# Sheet2.net
KiCad netlist of a schematic drawn in Altium Designer
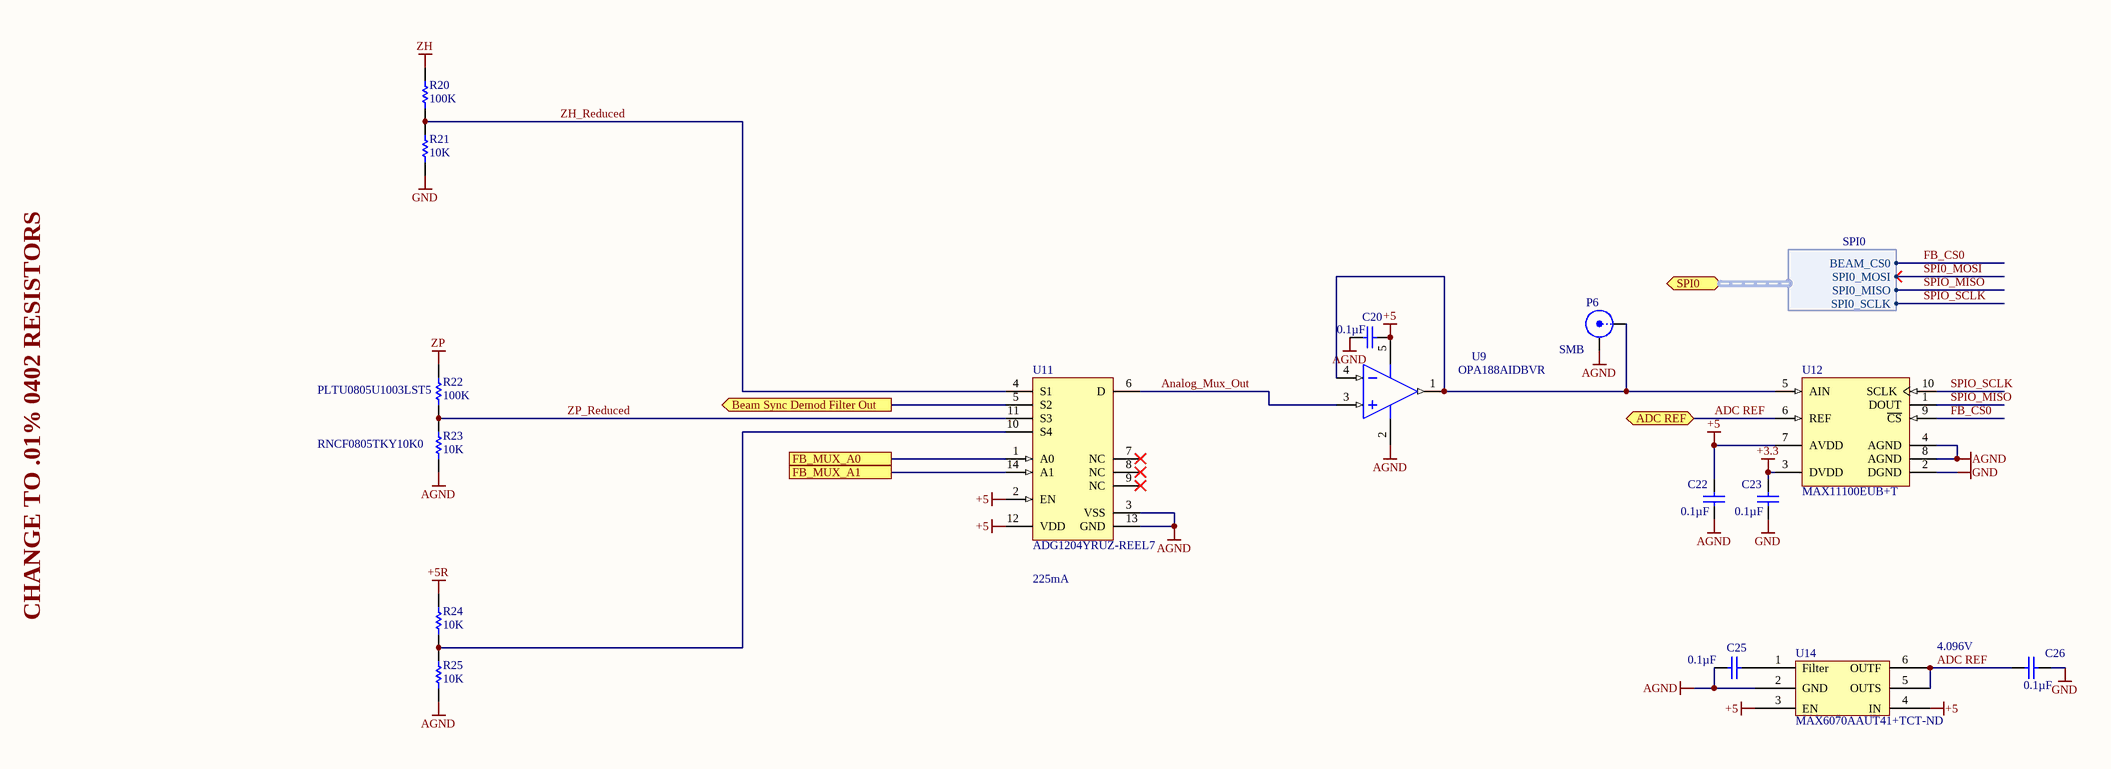
[diagram p0: Sheet2.SchDoc]

(export (version "E")
  (design (tool "Eeschema 10.0.6"))
  (components
    (comp (ref "C20")
      (value "CAP CER 0.1UF 25V X7R 0805")
      (footprint "CAPC0805(2012)145_N")
      (fields
        (field (name "MANUFACTURER") "Murata Electronics North America")
        (field (name "MANUFACTURER PART NUMBER") "GRM21BR71E104KA01L")
        (field (name "CAPACITANCE") "0.1µF")
        (field (name "TOLERANCE") "±10%")
      )
      (libsource (lib "Altium Content Vault") (part "CMP-1036-04795-1"))
    )
    (comp (ref "C22")
      (value "CAP CER 0.1UF 25V X7R 0805")
      (footprint "CAPC0805(2012)145_N")
      (fields
        (field (name "MANUFACTURER") "Murata Electronics North America")
        (field (name "MANUFACTURER PART NUMBER") "GRM21BR71E104KA01L")
        (field (name "CAPACITANCE") "0.1µF")
        (field (name "TOLERANCE") "±10%")
      )
      (libsource (lib "Altium Content Vault") (part "CMP-1036-04795-1"))
    )
    (comp (ref "C23")
      (value "CAP CER 0.1UF 25V X7R 0805")
      (footprint "CAPC0805(2012)145_N")
      (fields
        (field (name "MANUFACTURER") "Murata Electronics North America")
        (field (name "MANUFACTURER PART NUMBER") "GRM21BR71E104KA01L")
        (field (name "CAPACITANCE") "0.1µF")
        (field (name "TOLERANCE") "±10%")
      )
      (libsource (lib "Altium Content Vault") (part "CMP-1036-04795-1"))
    )
    (comp (ref "C25")
      (value "CAP CER 0.1UF 25V X7R 0805")
      (footprint "CAPC0805(2012)145_N")
      (fields
        (field (name "MANUFACTURER") "Murata Electronics North America")
        (field (name "MANUFACTURER PART NUMBER") "GRM21BR71E104KA01L")
        (field (name "CAPACITANCE") "0.1µF")
        (field (name "TOLERANCE") "±10%")
      )
      (libsource (lib "Altium Content Vault") (part "CMP-1036-04795-1"))
    )
    (comp (ref "C26")
      (value "CAP CER 0.1UF 25V X7R 0805")
      (footprint "CAPC0805(2012)145_N")
      (fields
        (field (name "MANUFACTURER") "Murata Electronics North America")
        (field (name "MANUFACTURER PART NUMBER") "GRM21BR71E104KA01L")
        (field (name "CAPACITANCE") "0.1µF")
        (field (name "TOLERANCE") "±10%")
      )
      (libsource (lib "Altium Content Vault") (part "CMP-1036-04795-1"))
    )
    (comp (ref "P6")
      (value "SMB")
      (footprint "RSP-122811-02")
      (description "SMB Straight Connector")
      (fields (field (name "PUBLISHER") "Altium Limited"))
      (libsource (lib "Miscellaneous Connectors") (part "SMB"))
    )
    (comp (ref "R20")
      (value "100K")
      (footprint "RESC0805(2012)_L")
      (description "RES SMD 100K OHM 1% 1/8W 0805")
      (fields
        (field (name "MANUFACTURER") "Vishay Dale")
        (field (name "MANUFACTURER PART NUMBER") "RCA0805100KFKEA")
      )
      (libsource (lib "Altium Content Vault") (part "CMP-1013-00215-1"))
    )
    (comp (ref "R21")
      (value "10K")
      (footprint "RESC0805(2012)_L")
      (description "RES SMD 10K OHM 1% 1/8W 0805")
      (fields
        (field (name "MANUFACTURER") "Vishay Dale")
        (field (name "MANUFACTURER PART NUMBER") "CRCW080510K0FKEA")
      )
      (libsource (lib "Altium Content Vault") (part "CMP-1013-00215-1"))
    )
    (comp (ref "R22")
      (value "100K")
      (footprint "RESC0805(2012)_L")
      (description "RES SMD 100K OHM 1% 1/8W 0805")
      (fields
        (field (name "MANUFACTURER") "Vishay Dale")
        (field (name "MANUFACTURER PART NUMBER") "RCA0805100KFKEA")
      )
      (libsource (lib "Altium Content Vault") (part "CMP-1013-00215-1"))
    )
    (comp (ref "R23")
      (value "10K")
      (footprint "RESC0805(2012)_L")
      (description "RES SMD 10K OHM 1% 1/8W 0805")
      (libsource (lib "Altium Content Vault") (part "CMP-1013-00215-1"))
    )
    (comp (ref "R24")
      (value "10K")
      (footprint "RESC0805(2012)_L")
      (description "RES SMD 10K OHM 1% 1/8W 0805")
      (fields
        (field (name "MANUFACTURER") "Vishay Dale")
        (field (name "MANUFACTURER PART NUMBER") "CRCW080510K0FKEA")
      )
      (libsource (lib "Altium Content Vault") (part "CMP-1013-00215-1"))
    )
    (comp (ref "R25")
      (value "10K")
      (footprint "RESC0805(2012)_L")
      (description "RES SMD 10K OHM 1% 1/8W 0805")
      (fields
        (field (name "MANUFACTURER") "Vishay Dale")
        (field (name "MANUFACTURER PART NUMBER") "CRCW080510K0FKEA")
      )
      (libsource (lib "Altium Content Vault") (part "CMP-1013-00215-1"))
    )
    (comp (ref "U9")
      (value "OPA188AIDBVR")
      (footprint "DBV0005A_M")
      (fields (field (name "MANUFACTURER") "Texas Instruments"))
      (libsource (lib "Altium Content Vault") (part "CMP-0809-00005-2"))
    )
    (comp (ref "U11")
      (value "ADG1204YRUZ-REEL7")
      (footprint "ADI-RU-14_L")
      (fields
        (field (name "MANUFACTURER") "Maxim Integrated")
        (field (name "MANUFACTURER PART NUMBER") "MAX11100EUB+")
        (field (name "BASE PART NUMBER") "MAX11100")
      )
      (libsource (lib "Altium Content Vault") (part "CMP-0793-00109-1"))
    )
    (comp (ref "U12")
      (value "MAX11100EUB+T")
      (footprint "U10+2_L")
      (description "16-Bit, +5V, 200ksps ADC with 10uA Shutdown, 10-Pin uMAX, -40°C to +85°C, Pb-Free, Tape and Reel")
      (fields
        (field (name "MANUFACTURER") "Maxim Integrated")
        (field (name "MANUFACTURER PART NUMBER") "MAX11100EUB+")
      )
      (libsource (lib "Altium Content Vault") (part "CMP-0249-00017-1"))
    )
    (comp (ref "U14")
      (value "MAX6070AAUT41+T")
      (footprint "SOT95P280X445-6N")
      (description "IC VREF SERIES 4.096V SOT23")
      (fields
        (field (name "SUPPLIER PART NUMBER 1") "MAX6070AAUT41+TCT-ND")
        (field (name "MANUFACTURER") "Maxim Integrated")
        (field (name "TOLERANCE") "±0.04%")
      )
      (libsource (lib "ZLS_Schematic_lib") (part "MAX6070AAUT41+T"))
    )
  )
  (nets
    (net (code "2") (name "+3.3") (class "Default")
      (node (ref "C23") (pin "1") (pinfunction "1_1") (pintype "passive"))
      (node (ref "U12") (pin "3") (pinfunction "DVDD_3") (pintype "power_in"))
    )
    (net (code "3") (name "+5") (class "Default")
      (node (ref "C20") (pin "2") (pinfunction "2_2") (pintype "passive"))
      (node (ref "C22") (pin "1") (pinfunction "1_1") (pintype "passive"))
      (node (ref "U11") (pin "12") (pinfunction "VDD_12") (pintype "power_in"))
      (node (ref "U11") (pin "2") (pinfunction "EN_2") (pintype "input"))
      (node (ref "U12") (pin "7") (pinfunction "AVDD_7") (pintype "power_in"))
      (node (ref "U14") (pin "3") (pinfunction "EN_3") (pintype "passive"))
      (node (ref "U14") (pin "4") (pinfunction "IN_4") (pintype "passive"))
      (node (ref "U9") (pin "5") (pinfunction "V+_5") (pintype "power_in"))
    )
    (net (code "4") (name "+5R") (class "Default")
      (node (ref "R24") (pin "2") (pinfunction "2_2") (pintype "passive"))
    )
    (net (code "5") (name "/ADC REF") (class "Default")
      (node (ref "C26") (pin "1") (pinfunction "1_1") (pintype "passive"))
      (node (ref "U12") (pin "6") (pinfunction "REF_6") (pintype "input"))
      (node (ref "U14") (pin "5") (pinfunction "OUTS_5") (pintype "passive"))
      (node (ref "U14") (pin "6") (pinfunction "OUTF_6") (pintype "passive"))
    )
    (net (code "6") (name "/Analog_Mux_Out") (class "Default")
      (node (ref "U11") (pin "6") (pinfunction "D_6") (pintype "passive"))
      (node (ref "U9") (pin "3") (pinfunction "IN+_3") (pintype "input"))
    )
    (net (code "7") (name "/Beam Sync Demod Filter Out") (class "Default")
      (node (ref "U11") (pin "5") (pinfunction "S2_5") (pintype "passive"))
    )
    (net (code "8") (name "/FB_CS0") (class "Default")
      (node (ref "U12") (pin "9") (pinfunction "~{CS}_9") (pintype "input"))
    )
    (net (code "9") (name "/FB_MUX_A0") (class "Default")
      (node (ref "U11") (pin "1") (pinfunction "A0_1") (pintype "input"))
    )
    (net (code "10") (name "/FB_MUX_A1") (class "Default")
      (node (ref "U11") (pin "14") (pinfunction "A1_14") (pintype "input"))
    )
    (net (code "12") (name "/SPIO_MISO") (class "Default")
      (node (ref "U12") (pin "1") (pinfunction "DOUT_1") (pintype "tri_state"))
    )
    (net (code "13") (name "/SPIO_SCLK") (class "Default")
      (node (ref "U12") (pin "10") (pinfunction "SCLK_10") (pintype "input"))
    )
    (net (code "14") (name "/ZH_Reduced") (class "Default")
      (node (ref "R20") (pin "1") (pinfunction "1_1") (pintype "passive"))
      (node (ref "R21") (pin "2") (pinfunction "2_2") (pintype "passive"))
      (node (ref "U11") (pin "4") (pinfunction "S1_4") (pintype "passive"))
    )
    (net (code "15") (name "/ZP_Reduced") (class "Default")
      (node (ref "R22") (pin "1") (pinfunction "1_1") (pintype "passive"))
      (node (ref "R23") (pin "2") (pinfunction "2_2") (pintype "passive"))
      (node (ref "U11") (pin "11") (pinfunction "S3_11") (pintype "passive"))
    )
    (net (code "17") (name "AGND") (class "Default")
      (node (ref "C20") (pin "1") (pinfunction "1_1") (pintype "passive"))
      (node (ref "C22") (pin "2") (pinfunction "2_2") (pintype "passive"))
      (node (ref "C25") (pin "1") (pinfunction "1_1") (pintype "passive"))
      (node (ref "P6") (pin "2") (pinfunction "Y_2") (pintype "passive"))
      (node (ref "R23") (pin "1") (pinfunction "1_1") (pintype "passive"))
      (node (ref "R25") (pin "1") (pinfunction "1_1") (pintype "passive"))
      (node (ref "U11") (pin "13") (pinfunction "GND_13") (pintype "power_in"))
      (node (ref "U11") (pin "3") (pinfunction "VSS_3") (pintype "power_in"))
      (node (ref "U12") (pin "4") (pinfunction "AGND_4") (pintype "power_in"))
      (node (ref "U12") (pin "8") (pinfunction "AGND_8") (pintype "power_in"))
      (node (ref "U14") (pin "2") (pinfunction "GND_2") (pintype "passive"))
      (node (ref "U9") (pin "2") (pinfunction "V-_2") (pintype "power_in"))
    )
    (net (code "18") (name "GND") (class "Default")
      (node (ref "C23") (pin "2") (pinfunction "2_2") (pintype "passive"))
      (node (ref "C26") (pin "2") (pinfunction "2_2") (pintype "passive"))
      (node (ref "R21") (pin "1") (pinfunction "1_1") (pintype "passive"))
      (node (ref "U12") (pin "2") (pinfunction "DGND_2") (pintype "power_in"))
    )
    (net (code "19") (name "Net-(P6-X)") (class "Default")
      (node (ref "P6") (pin "1") (pinfunction "X_1") (pintype "passive"))
      (node (ref "U12") (pin "5") (pinfunction "AIN_5") (pintype "input"))
      (node (ref "U9") (pin "1") (pinfunction "OUT_1") (pintype "output"))
      (node (ref "U9") (pin "4") (pinfunction "IN-_4") (pintype "input"))
    )
    (net (code "20") (name "Net-(U11-S4)") (class "Default")
      (node (ref "R24") (pin "1") (pinfunction "1_1") (pintype "passive"))
      (node (ref "R25") (pin "2") (pinfunction "2_2") (pintype "passive"))
      (node (ref "U11") (pin "10") (pinfunction "S4_10") (pintype "passive"))
    )
    (net (code "21") (name "Net-(U14-Filter)") (class "Default")
      (node (ref "C25") (pin "2") (pinfunction "2_2") (pintype "passive"))
      (node (ref "U14") (pin "1") (pinfunction "Filter_1") (pintype "passive"))
    )
    (net (code "22") (name "ZH") (class "Default")
      (node (ref "R20") (pin "2") (pinfunction "2_2") (pintype "passive"))
    )
    (net (code "23") (name "ZP") (class "Default")
      (node (ref "R22") (pin "2") (pinfunction "2_2") (pintype "passive"))
    )
    (net (code "24") (name "unconnected-(U11-NC-Pad7)") (class "Default")
      (node (ref "U11") (pin "7") (pinfunction "NC_7") (pintype "passive+no_connect"))
    )
    (net (code "25") (name "unconnected-(U11-NC-Pad8)") (class "Default")
      (node (ref "U11") (pin "8") (pinfunction "NC_8") (pintype "passive+no_connect"))
    )
    (net (code "26") (name "unconnected-(U11-NC-Pad9)") (class "Default")
      (node (ref "U11") (pin "9") (pinfunction "NC_9") (pintype "passive+no_connect"))
    )
  )
)
